# Connectors.net
KiCad netlist of a schematic drawn in Altium Designer
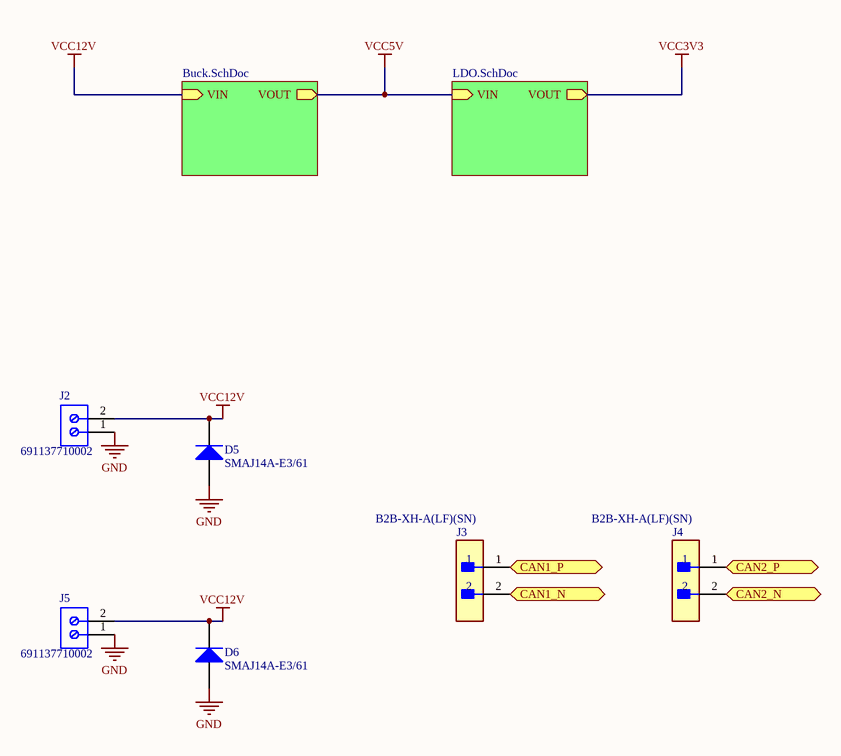
[diagram p0: Connectors.SchDoc]

(export (version "E")
  (design (tool "Eeschema 10.0.6"))
  (components
    (comp (ref "D5")
      (value "SMAJ14A-E3/61")
      (footprint "VISH-DO-214AC-2_L")
      (fields (field (name "MANUFACTURER") "Vishay Semiconductor"))
      (libsource (lib "Altium Content Vault") (part "VISH-K1A2-2"))
    )
    (comp (ref "D6")
      (value "SMAJ14A-E3/61")
      (footprint "VISH-DO-214AC-2_L")
      (fields (field (name "MANUFACTURER") "Vishay Semiconductor"))
      (libsource (lib "Altium Content Vault") (part "VISH-K1A2-2"))
    )
    (comp (ref "J2")
      (value "691137710002")
      (footprint "691137710002")
      (libsource (lib "Altium Content Vault") (part "TBL - 1R - 02P - Screw"))
    )
    (comp (ref "J3")
      (value "B2B-XH-A(LF)(SN)")
      (footprint "FP-B2B-XH-A_LF_SN-MFG")
      (description "CONN HEADER VERT 2POS 2.5MM")
      (libsource (lib "Altium Content Vault") (part "3bc925449376181038e59eaffc5286c"))
    )
    (comp (ref "J4")
      (value "B2B-XH-A(LF)(SN)")
      (footprint "FP-B2B-XH-A_LF_SN-MFG")
      (description "CONN HEADER VERT 2POS 2.5MM")
      (libsource (lib "Altium Content Vault") (part "3bc925449376181038e59eaffc5286c"))
    )
    (comp (ref "J5")
      (value "691137710002")
      (footprint "691137710002")
      (libsource (lib "Altium Content Vault") (part "TBL - 1R - 02P - Screw"))
    )
  )
  (nets
    (net (code "1") (name "/CAN1_N") (class "Default")
      (node (ref "J3") (pin "2") (pinfunction "2_2") (pintype "passive"))
    )
    (net (code "2") (name "/CAN1_P") (class "Default")
      (node (ref "J3") (pin "1") (pinfunction "1_1") (pintype "passive"))
    )
    (net (code "3") (name "/CAN2_N") (class "Default")
      (node (ref "J4") (pin "2") (pinfunction "2_2") (pintype "passive"))
    )
    (net (code "4") (name "/CAN2_P") (class "Default")
      (node (ref "J4") (pin "1") (pinfunction "1_1") (pintype "passive"))
    )
    (net (code "5") (name "GND") (class "Default")
      (node (ref "D5") (pin "2") (pinfunction "A_2") (pintype "passive"))
      (node (ref "D6") (pin "2") (pinfunction "A_2") (pintype "passive"))
      (node (ref "J2") (pin "1") (pinfunction "1_1") (pintype "passive"))
      (node (ref "J5") (pin "1") (pinfunction "1_1") (pintype "passive"))
    )
    (net (code "8") (name "VCC12V") (class "Default")
      (node (ref "D5") (pin "1") (pinfunction "K_1") (pintype "passive"))
      (node (ref "D6") (pin "1") (pinfunction "K_1") (pintype "passive"))
      (node (ref "J2") (pin "2") (pinfunction "2_2") (pintype "passive"))
      (node (ref "J5") (pin "2") (pinfunction "2_2") (pintype "passive"))
    )
  )
)
